# ESP8266_usb_spi_connector.net
KiCad netlist of a schematic drawn in EAGLE
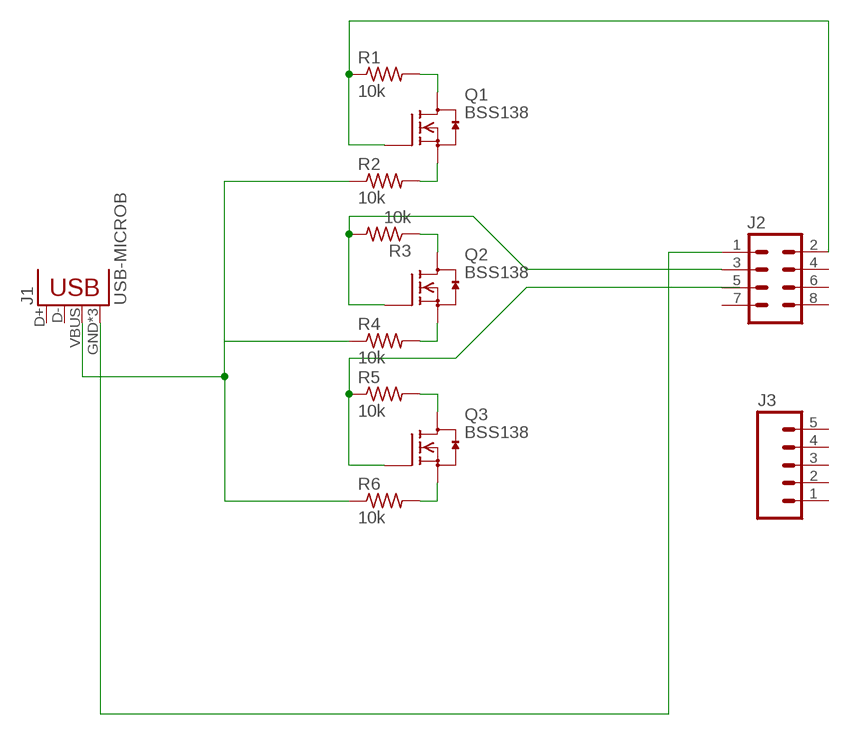
[diagram p0: schematic, sheet 1]

(export (version "E")
  (design (tool "Eeschema 10.0.6"))
  (components
    (comp (ref "J1")
      (value "USB-MICROB")
      (footprint "eagle-import:USB-MICROB")
      (libsource (lib "eagle-import") (part "USB-MICROB"))
    )
    (comp (ref "J2")
      (value "M04X2")
      (footprint "eagle-import:2X4")
      (libsource (lib "eagle-import") (part "M04X2"))
    )
    (comp (ref "J3")
      (value "M05PTH")
      (footprint "eagle-import:1X05")
      (libsource (lib "eagle-import") (part "M05PTH"))
    )
    (comp (ref "Q1")
      (value "BSS138")
      (footprint "eagle-import:SOT23")
      (libsource (lib "eagle-import") (part "BSS138"))
    )
    (comp (ref "Q2")
      (value "BSS138")
      (footprint "eagle-import:SOT23")
      (libsource (lib "eagle-import") (part "BSS138"))
    )
    (comp (ref "Q3")
      (value "BSS138")
      (footprint "eagle-import:SOT23")
      (libsource (lib "eagle-import") (part "BSS138"))
    )
    (comp (ref "R1")
      (value "10k")
      (footprint "eagle-import:M1206")
      (libsource (lib "eagle-import") (part "R-US_M1206"))
    )
    (comp (ref "R2")
      (value "10k")
      (footprint "eagle-import:M1206")
      (libsource (lib "eagle-import") (part "R-US_M1206"))
    )
    (comp (ref "R3")
      (value "10k")
      (footprint "eagle-import:M1206")
      (libsource (lib "eagle-import") (part "R-US_M1206"))
    )
    (comp (ref "R4")
      (value "10k")
      (footprint "eagle-import:M1206")
      (libsource (lib "eagle-import") (part "R-US_M1206"))
    )
    (comp (ref "R5")
      (value "10k")
      (footprint "eagle-import:M1206")
      (libsource (lib "eagle-import") (part "R-US_M1206"))
    )
    (comp (ref "R6")
      (value "10k")
      (footprint "eagle-import:M1206")
      (libsource (lib "eagle-import") (part "R-US_M1206"))
    )
  )
  (nets
    (net (code "1") (name "Net-(J1-GND-PadMT1)") (class "Default")
      (node (ref "J1") (pin "GND") (pinfunction "GND_GND") (pintype "bidirectional"))
      (node (ref "J1") (pin "MT1") (pinfunction "GND_MT1") (pintype "bidirectional"))
      (node (ref "J1") (pin "MT2") (pinfunction "GND_MT2") (pintype "bidirectional"))
      (node (ref "J2") (pin "1") (pinfunction "1_1") (pintype "passive"))
    )
    (net (code "2") (name "Net-(J1-PadVBUS)") (class "Default")
      (node (ref "J1") (pin "VBUS") (pinfunction "VBUS_VBUS") (pintype "bidirectional"))
      (node (ref "R2") (pin "1") (pinfunction "1_1") (pintype "passive"))
      (node (ref "R4") (pin "1") (pinfunction "1_1") (pintype "passive"))
      (node (ref "R6") (pin "1") (pinfunction "1_1") (pintype "passive"))
    )
    (net (code "3") (name "Net-(Q1-D)") (class "Default")
      (node (ref "Q1") (pin "3") (pinfunction "D_3") (pintype "passive"))
      (node (ref "R1") (pin "2") (pinfunction "2_2") (pintype "passive"))
    )
    (net (code "4") (name "Net-(Q1-G)") (class "Default")
      (node (ref "J2") (pin "2") (pinfunction "2_2") (pintype "passive"))
      (node (ref "Q1") (pin "1") (pinfunction "G_1") (pintype "passive"))
      (node (ref "R1") (pin "1") (pinfunction "1_1") (pintype "passive"))
    )
    (net (code "5") (name "Net-(Q1-S)") (class "Default")
      (node (ref "Q1") (pin "2") (pinfunction "S_2") (pintype "passive"))
      (node (ref "R2") (pin "2") (pinfunction "2_2") (pintype "passive"))
    )
    (net (code "6") (name "Net-(Q2-D)") (class "Default")
      (node (ref "Q2") (pin "3") (pinfunction "D_3") (pintype "passive"))
      (node (ref "R3") (pin "1") (pinfunction "1_1") (pintype "passive"))
    )
    (net (code "7") (name "Net-(Q2-G)") (class "Default")
      (node (ref "J2") (pin "3") (pinfunction "3_3") (pintype "passive"))
      (node (ref "Q2") (pin "1") (pinfunction "G_1") (pintype "passive"))
      (node (ref "R3") (pin "2") (pinfunction "2_2") (pintype "passive"))
    )
    (net (code "8") (name "Net-(Q2-S)") (class "Default")
      (node (ref "Q2") (pin "2") (pinfunction "S_2") (pintype "passive"))
      (node (ref "R4") (pin "2") (pinfunction "2_2") (pintype "passive"))
    )
    (net (code "9") (name "Net-(Q3-D)") (class "Default")
      (node (ref "Q3") (pin "3") (pinfunction "D_3") (pintype "passive"))
      (node (ref "R5") (pin "2") (pinfunction "2_2") (pintype "passive"))
    )
    (net (code "10") (name "Net-(Q3-G)") (class "Default")
      (node (ref "Q3") (pin "1") (pinfunction "G_1") (pintype "passive"))
      (node (ref "R5") (pin "1") (pinfunction "1_1") (pintype "passive"))
    )
    (net (code "11") (name "Net-(Q3-S)") (class "Default")
      (node (ref "Q3") (pin "2") (pinfunction "S_2") (pintype "passive"))
      (node (ref "R6") (pin "2") (pinfunction "2_2") (pintype "passive"))
    )
    (net (code "12") (name "unconnected-(J1-PadD+)") (class "Default")
      (node (ref "J1") (pin "D+") (pinfunction "D+_D+") (pintype "bidirectional"))
    )
    (net (code "13") (name "unconnected-(J1-PadD-)") (class "Default")
      (node (ref "J1") (pin "D-") (pinfunction "D-_D-") (pintype "bidirectional"))
    )
    (net (code "14") (name "unconnected-(J2-Pad4)") (class "Default")
      (node (ref "J2") (pin "4") (pinfunction "4_4") (pintype "passive"))
    )
    (net (code "15") (name "unconnected-(J2-Pad5)") (class "Default")
      (node (ref "J2") (pin "5") (pinfunction "5_5") (pintype "passive"))
    )
    (net (code "16") (name "unconnected-(J2-Pad6)") (class "Default")
      (node (ref "J2") (pin "6") (pinfunction "6_6") (pintype "passive"))
    )
    (net (code "17") (name "unconnected-(J2-Pad7)") (class "Default")
      (node (ref "J2") (pin "7") (pinfunction "7_7") (pintype "passive"))
    )
    (net (code "18") (name "unconnected-(J2-Pad8)") (class "Default")
      (node (ref "J2") (pin "8") (pinfunction "8_8") (pintype "passive"))
    )
    (net (code "19") (name "unconnected-(J3-Pad1)") (class "Default")
      (node (ref "J3") (pin "1") (pinfunction "1_1") (pintype "passive"))
    )
    (net (code "20") (name "unconnected-(J3-Pad2)") (class "Default")
      (node (ref "J3") (pin "2") (pinfunction "2_2") (pintype "passive"))
    )
    (net (code "21") (name "unconnected-(J3-Pad3)") (class "Default")
      (node (ref "J3") (pin "3") (pinfunction "3_3") (pintype "passive"))
    )
    (net (code "22") (name "unconnected-(J3-Pad4)") (class "Default")
      (node (ref "J3") (pin "4") (pinfunction "4_4") (pintype "passive"))
    )
    (net (code "23") (name "unconnected-(J3-Pad5)") (class "Default")
      (node (ref "J3") (pin "5") (pinfunction "5_5") (pintype "passive"))
    )
  )
)
